# Mainboard.net
KiCad netlist of a schematic drawn in Altium Designer
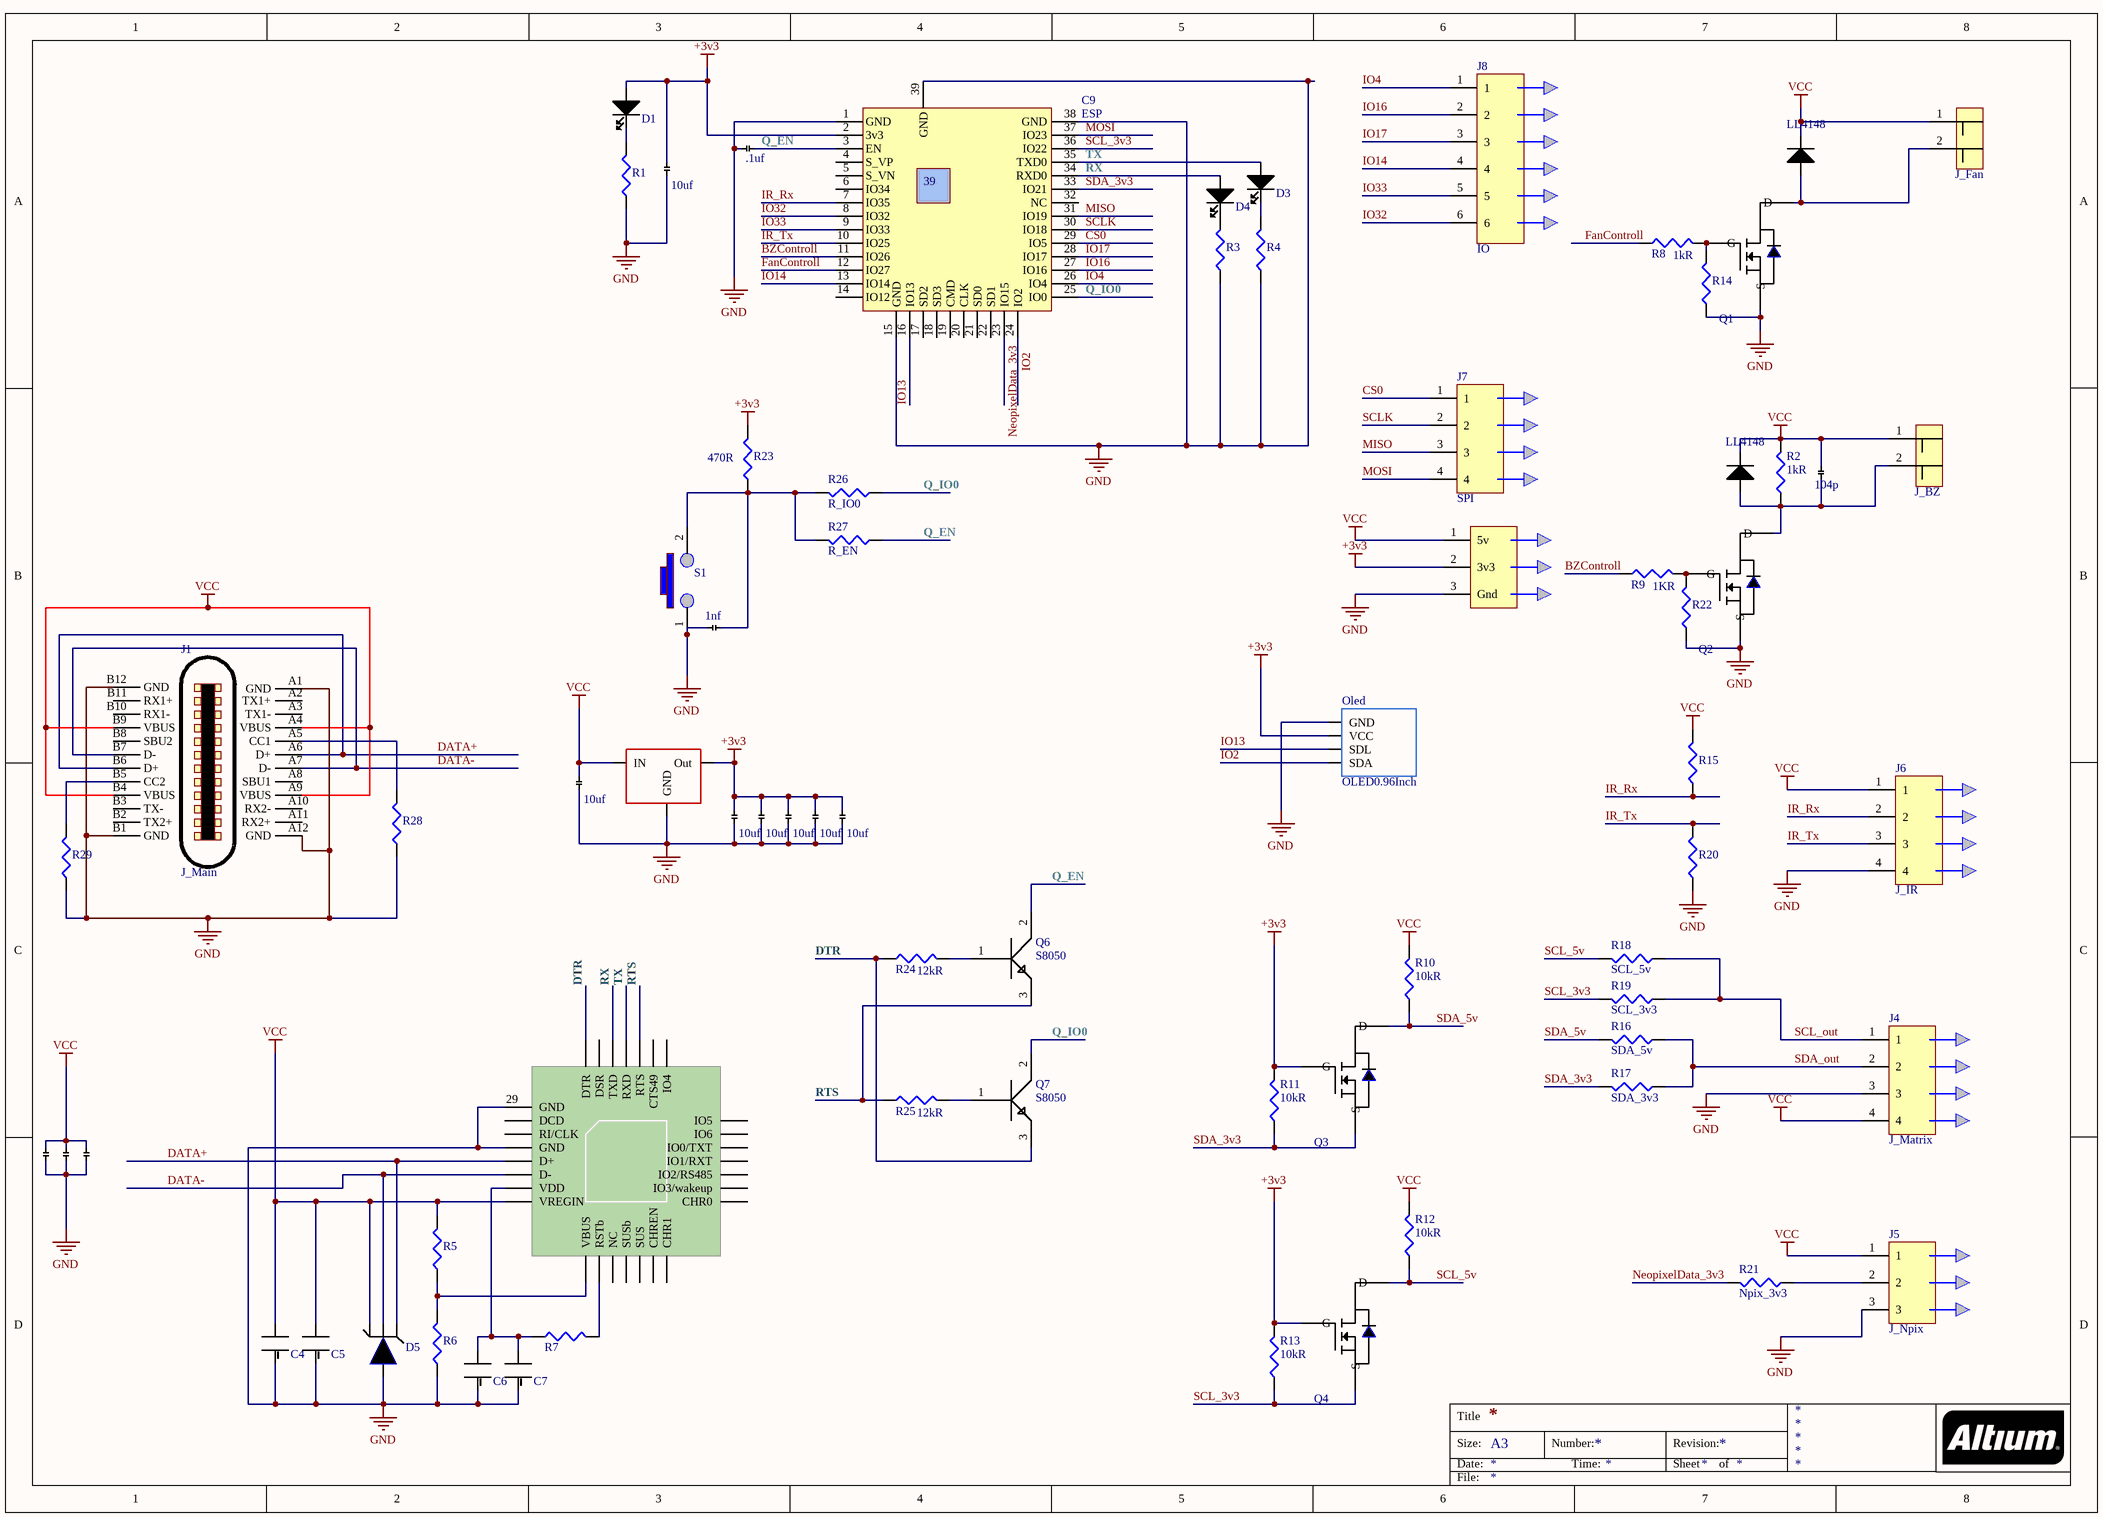
[diagram p0: Mainboard.SchDoc]

(export (version "E")
  (design (tool "Eeschema 10.0.6"))
  (components
    (comp (ref "C1")
      (value "104p")
      (footprint "Capacitor0805")
      (description "for leds and smol")
      (libsource (lib "WolfgasmScheLib") (part "capacitor0.1uf"))
    )
    (comp (ref "C2")
      (value "104p")
      (footprint "Capacitor0805")
      (description "for leds and smol")
      (libsource (lib "WolfgasmScheLib") (part "capacitor0.1uf"))
    )
    (comp (ref "C3")
      (value "104p")
      (footprint "Capacitor0805")
      (description "for leds and smol")
      (libsource (lib "WolfgasmScheLib") (part "capacitor0.1uf"))
    )
    (comp (ref "C4")
      (value "C4R7")
      (footprint "Capacitor0603")
      (description "Cap Ceramic 4.7uF 6.3V X5R 20% Pad SMD 0402 85C T/R")
      (fields (field (name "TOLERANCE") "20%"))
      (libsource (lib "WTFschlibra") (part "capacitor0603"))
    )
    (comp (ref "C5")
      (value "C104")
      (footprint "Capacitor0603")
      (description "0.1uf")
      (fields (field (name "TOLERANCE") "20%"))
      (libsource (lib "WTFschlibra") (part "capacitor0603"))
    )
    (comp (ref "C6")
      (value "C104")
      (footprint "Capacitor0603")
      (description "4.7")
      (fields (field (name "TOLERANCE") "20%"))
      (libsource (lib "WTFschlibra") (part "capacitor0603"))
    )
    (comp (ref "C7")
      (value "C4R7")
      (footprint "Capacitor0603")
      (description "0.1")
      (fields (field (name "TOLERANCE") "20%"))
      (libsource (lib "WTFschlibra") (part "capacitor0603"))
    )
    (comp (ref "C8")
      (value "104p")
      (footprint "Capacitor0805")
      (description "for leds and smol")
      (libsource (lib "WolfgasmScheLib") (part "capacitor0.1uf"))
    )
    (comp (ref "C9")
      (value "ESP")
      (footprint "ESP_WROOM_32_BARED_CHIP")
      (libsource (lib "WolfgasmScheLib") (part "ESP_wroom32_bared_chip"))
    )
    (comp (ref "C10")
      (value "1nf")
      (footprint "Capacitor0805")
      (description "for leds and smol")
      (libsource (lib "WolfgasmScheLib") (part "capacitor0.1uf"))
    )
    (comp (ref "C11")
      (value "10uf")
      (footprint "Capacitor0805")
      (description "for leds and smol")
      (libsource (lib "WolfgasmScheLib") (part "capacitor0.1uf"))
    )
    (comp (ref "C12")
      (value "10uf")
      (footprint "Capacitor0805")
      (description "for leds and smol")
      (libsource (lib "WolfgasmScheLib") (part "capacitor0.1uf"))
    )
    (comp (ref "C13")
      (value "10uf")
      (footprint "Capacitor0805")
      (description "for leds and smol")
      (libsource (lib "WolfgasmScheLib") (part "capacitor0.1uf"))
    )
    (comp (ref "C14")
      (value "10uf")
      (footprint "Capacitor0805")
      (description "for leds and smol")
      (libsource (lib "WolfgasmScheLib") (part "capacitor0.1uf"))
    )
    (comp (ref "C15")
      (value "10uf")
      (footprint "Capacitor0805")
      (description "for leds and smol")
      (libsource (lib "WolfgasmScheLib") (part "capacitor0.1uf"))
    )
    (comp (ref "C16")
      (value "10uf")
      (footprint "Capacitor0805")
      (description "for leds and smol")
      (libsource (lib "WolfgasmScheLib") (part "capacitor0.1uf"))
    )
    (comp (ref "C17")
      (value "10uf")
      (footprint "Capacitor0805")
      (description "for leds and smol")
      (libsource (lib "WolfgasmScheLib") (part "capacitor0.1uf"))
    )
    (comp (ref "C18")
      (value ".1uf")
      (footprint "Capacitor0805")
      (description "for leds and smol")
      (libsource (lib "WolfgasmScheLib") (part "capacitor0.1uf"))
    )
    (comp (ref "cp1")
      (value "CP2102N")
      (footprint "CP2102N_QFN28")
      (description "Full Speed USB to UART Bridge USB 2.0 3.3V T/R Automotive 28-Pin QFN EP")
      (libsource (lib "WTFschlibra") (part "CP2102N-A02-GQFN28R"))
    )
    (comp (ref "D1")
      (value "ESP")
      (footprint "LED0603")
      (description "LED BLUE CLEAR CHIP SMD")
      (libsource (lib "WTFschlibra") (part "LTST-C190TBKT"))
    )
    (comp (ref "D2")
      (value "LL4148")
      (footprint "SOD80-LL4148")
      (description "ON SEMICONDUCTOR - LL4148 - Small Signal Diode, Single, 100 V, 200 mA, 1 V, 4 ns, 2 A")
      (fields (field (name "VOLTAGE") "100V"))
      (libsource (lib "WolfgasmScheLib") (part "LL4148"))
    )
    (comp (ref "D3")
      (value "TXD")
      (footprint "LED0603")
      (description "LED BLUE CLEAR CHIP SMD")
      (libsource (lib "WTFschlibra") (part "LTST-C190TBKT"))
    )
    (comp (ref "D4")
      (value "RXD")
      (footprint "LED0603")
      (description "LED BLUE CLEAR CHIP SMD")
      (libsource (lib "WTFschlibra") (part "LTST-C190TBKT"))
    )
    (comp (ref "D5")
      (value "SP0503BAHTG")
      (footprint "SP0503BAHTG - SOT143-4")
      (description "ESD Suppressor TVS 5.5V 4-Pin(3+Tab) SOT-143 T/R")
      (libsource (lib "WTFschlibra") (part "SP0503BAHTG"))
    )
    (comp (ref "D6")
      (value "LL4148")
      (footprint "SOD80-LL4148")
      (description "ON SEMICONDUCTOR - LL4148 - Small Signal Diode, Single, 100 V, 200 mA, 1 V, 4 ns, 2 A")
      (fields (field (name "VOLTAGE") "100V"))
      (libsource (lib "WolfgasmScheLib") (part "LL4148"))
    )
    (comp (ref "J1")
      (value "J_Main")
      (footprint "USB_C_24P_SMT")
      (libsource (lib "WolfgasmScheLib") (part "USB_TypeC_24P"))
    )
    (comp (ref "J2")
      (value "J_BZ")
      (footprint "1x2 S2B-XH")
      (libsource (lib "WolfgasmScheLib") (part "S2B-XH"))
    )
    (comp (ref "J3")
      (value "J_Fan")
      (footprint "1x2 S2B-XH")
      (libsource (lib "WolfgasmScheLib") (part "S2B-XH"))
    )
    (comp (ref "J4")
      (value "J_Matrix")
      (footprint "1x4 DUPONT RightAngle")
      (libsource (lib "WolfgasmScheLib") (part "1x4 dupont general"))
    )
    (comp (ref "J5")
      (value "J_Npix")
      (footprint "1x3 2.54 big chunk verticle")
      (libsource (lib "WolfgasmScheLib") (part "1x3 2.54 chunk verticle"))
    )
    (comp (ref "J6")
      (value "J_IR")
      (footprint "Xh 2.54 4 Pin Right")
      (libsource (lib "WolfgasmScheLib") (part "1x4 general Header"))
    )
    (comp (ref "J7")
      (value "SPI")
      (footprint "1x4 DUPONT RightAngle")
      (libsource (lib "WolfgasmScheLib") (part "1x4 general Header"))
    )
    (comp (ref "J8")
      (value "IO")
      (footprint "1x6 dupont right angle")
      (libsource (lib "WolfgasmScheLib") (part "1x6 general dupont"))
    )
    (comp (ref "J9")
      (value "power")
      (footprint "1x3 dupont right angle")
      (libsource (lib "WolfgasmScheLib") (part "1x3 dupont power"))
    )
    (comp (ref "Oled")
      (value "OLED0.96Inch")
      (footprint "0.96OLED")
      (libsource (lib "WolfgasmScheLib") (part "OLED0.96Inch"))
    )
    (comp (ref "Q1")
      (value "Bss133")
      (footprint "SOT_23")
      (libsource (lib "WolfgasmScheLib") (part "Bss138 Mosfet"))
    )
    (comp (ref "Q2")
      (value "Bss133")
      (footprint "SOT_23")
      (libsource (lib "WolfgasmScheLib") (part "Bss138 Mosfet"))
    )
    (comp (ref "Q3")
      (value "Bss133")
      (footprint "SOT_23")
      (libsource (lib "WolfgasmScheLib") (part "Bss138 Mosfet"))
    )
    (comp (ref "Q4")
      (value "Bss133")
      (footprint "SOT_23")
      (libsource (lib "WolfgasmScheLib") (part "Bss138 Mosfet"))
    )
    (comp (ref "Q5")
      (value "lm1117")
      (footprint "SOT-223")
      (libsource (lib "WolfgasmScheLib") (part "LM1117-3.3v"))
    )
    (comp (ref "Q6")
      (value "S8050")
      (footprint "SOT_23")
      (libsource (lib "WolfgasmScheLib") (part "S8050NPN"))
    )
    (comp (ref "Q7")
      (value "S8050")
      (footprint "SOT_23")
      (libsource (lib "WolfgasmScheLib") (part "S8050NPN"))
    )
    (comp (ref "R1")
      (value "360R")
      (footprint "R0805")
      (description "Res Thick Film 0805 360 Ohm 1% 0.125W(1/8W) ±100ppm/C Molded SMD Automotive Paper T/R")
      (fields (field (name "TOLERANCE") "1%"))
      (libsource (lib "WTFschlibra") (part "CRCW0805360RFKEA"))
    )
    (comp (ref "R2")
      (value "1kR")
      (footprint "R0805")
      (description "Res Thick Film 0805 360 Ohm 1% 0.125W(1/8W) ±100ppm/C Molded SMD Automotive Paper T/R")
      (fields (field (name "TOLERANCE") "1%"))
      (libsource (lib "WolfgasmScheLib") (part "resistor(CRCW0805360RFKEA"))
    )
    (comp (ref "R3")
      (value "R360")
      (footprint "R0805")
      (description "Res Thick Film 0805 360 Ohm 1% 0.125W(1/8W) ±100ppm/C Molded SMD Automotive Paper T/R")
      (fields (field (name "TOLERANCE") "1%"))
      (libsource (lib "WTFschlibra") (part "CRCW0805360RFKEA"))
    )
    (comp (ref "R4")
      (value "R360")
      (footprint "R0805")
      (description "Res Thick Film 0805 360 Ohm 1% 0.125W(1/8W) ±100ppm/C Molded SMD Automotive Paper T/R")
      (fields (field (name "TOLERANCE") "1%"))
      (libsource (lib "WTFschlibra") (part "CRCW0805360RFKEA"))
    )
    (comp (ref "R5")
      (value "R2212")
      (footprint "R0805")
      (description "Res Thick Film 0805 360 Ohm 1% 0.125W(1/8W) ±100ppm/C Molded SMD Automotive Paper T/R")
      (fields (field (name "TOLERANCE") "1%"))
      (libsource (lib "WTFschlibra") (part "resistor(CRCW0805360RFKEA"))
    )
    (comp (ref "R6")
      (value "R4752")
      (footprint "R0805")
      (description "Res Thick Film 0805 360 Ohm 1% 0.125W(1/8W) ±100ppm/C Molded SMD Automotive Paper T/R")
      (fields (field (name "TOLERANCE") "1%"))
      (libsource (lib "WTFschlibra") (part "resistor(CRCW0805360RFKEA"))
    )
    (comp (ref "R7")
      (value "R102")
      (footprint "R0805")
      (description "1Kohms")
      (fields (field (name "TOLERANCE") "1%"))
      (libsource (lib "WTFschlibra") (part "resistor(CRCW0805360RFKEA"))
    )
    (comp (ref "R8")
      (value "1kR")
      (footprint "R0805")
      (description "Res Thick Film 0805 360 Ohm 1% 0.125W(1/8W) ±100ppm/C Molded SMD Automotive Paper T/R")
      (fields (field (name "TOLERANCE") "1%"))
      (libsource (lib "WolfgasmScheLib") (part "resistor(CRCW0805360RFKEA"))
    )
    (comp (ref "R9")
      (value "1KR")
      (footprint "R0805")
      (description "Res Thick Film 0805 360 Ohm 1% 0.125W(1/8W) ±100ppm/C Molded SMD Automotive Paper T/R")
      (fields (field (name "TOLERANCE") "1%"))
      (libsource (lib "WolfgasmScheLib") (part "resistor(CRCW0805360RFKEA"))
    )
    (comp (ref "R10")
      (value "10kR")
      (footprint "R0805")
      (description "Res Thick Film 0805 360 Ohm 1% 0.125W(1/8W) ±100ppm/C Molded SMD Automotive Paper T/R")
      (fields (field (name "TOLERANCE") "1%"))
      (libsource (lib "WolfgasmScheLib") (part "resistor(CRCW0805360RFKEA"))
    )
    (comp (ref "R11")
      (value "10kR")
      (footprint "R0805")
      (description "Res Thick Film 0805 360 Ohm 1% 0.125W(1/8W) ±100ppm/C Molded SMD Automotive Paper T/R")
      (fields (field (name "TOLERANCE") "1%"))
      (libsource (lib "WolfgasmScheLib") (part "resistor(CRCW0805360RFKEA"))
    )
    (comp (ref "R12")
      (value "10kR")
      (footprint "R0805")
      (description "Res Thick Film 0805 360 Ohm 1% 0.125W(1/8W) ±100ppm/C Molded SMD Automotive Paper T/R")
      (fields (field (name "TOLERANCE") "1%"))
      (libsource (lib "WolfgasmScheLib") (part "resistor(CRCW0805360RFKEA"))
    )
    (comp (ref "R13")
      (value "10kR")
      (footprint "R0805")
      (description "Res Thick Film 0805 360 Ohm 1% 0.125W(1/8W) ±100ppm/C Molded SMD Automotive Paper T/R")
      (fields (field (name "TOLERANCE") "1%"))
      (libsource (lib "WolfgasmScheLib") (part "resistor(CRCW0805360RFKEA"))
    )
    (comp (ref "R14")
      (value "10kR")
      (footprint "R0805")
      (description "Res Thick Film 0805 360 Ohm 1% 0.125W(1/8W) ±100ppm/C Molded SMD Automotive Paper T/R")
      (fields (field (name "TOLERANCE") "1%"))
      (libsource (lib "WTFschlibra") (part "CRCW0805360RFKEA"))
    )
    (comp (ref "R15")
      (value "10kR")
      (footprint "R0805")
      (description "Res Thick Film 0805 360 Ohm 1% 0.125W(1/8W) ±100ppm/C Molded SMD Automotive Paper T/R")
      (fields (field (name "TOLERANCE") "1%"))
      (libsource (lib "WTFschlibra") (part "CRCW0805360RFKEA"))
    )
    (comp (ref "R16")
      (value "SDA_5v")
      (footprint "R0805")
      (description "Res Thick Film 0805 360 Ohm 1% 0.125W(1/8W) ±100ppm/C Molded SMD Automotive Paper T/R")
      (fields (field (name "TOLERANCE") "1%"))
      (libsource (lib "WolfgasmScheLib") (part "resistor(CRCW0805360RFKEA"))
    )
    (comp (ref "R17")
      (value "SDA_3v3")
      (footprint "R0805")
      (description "Res Thick Film 0805 360 Ohm 1% 0.125W(1/8W) ±100ppm/C Molded SMD Automotive Paper T/R")
      (fields (field (name "TOLERANCE") "1%"))
      (libsource (lib "WolfgasmScheLib") (part "resistor(CRCW0805360RFKEA"))
    )
    (comp (ref "R18")
      (value "SCL_5v")
      (footprint "R0805")
      (description "Res Thick Film 0805 360 Ohm 1% 0.125W(1/8W) ±100ppm/C Molded SMD Automotive Paper T/R")
      (fields (field (name "TOLERANCE") "1%"))
      (libsource (lib "WolfgasmScheLib") (part "resistor(CRCW0805360RFKEA"))
    )
    (comp (ref "R19")
      (value "SCL_3v3")
      (footprint "R0805")
      (description "Res Thick Film 0805 360 Ohm 1% 0.125W(1/8W) ±100ppm/C Molded SMD Automotive Paper T/R")
      (fields (field (name "TOLERANCE") "1%"))
      (libsource (lib "WolfgasmScheLib") (part "resistor(CRCW0805360RFKEA"))
    )
    (comp (ref "R20")
      (value "10kR")
      (footprint "R0805")
      (description "Res Thick Film 0805 360 Ohm 1% 0.125W(1/8W) ±100ppm/C Molded SMD Automotive Paper T/R")
      (fields (field (name "TOLERANCE") "1%"))
      (libsource (lib "WTFschlibra") (part "CRCW0805360RFKEA"))
    )
    (comp (ref "R21")
      (value "Npix_3v3")
      (footprint "R0805")
      (description "Res Thick Film 0805 360 Ohm 1% 0.125W(1/8W) ±100ppm/C Molded SMD Automotive Paper T/R")
      (fields (field (name "TOLERANCE") "1%"))
      (libsource (lib "WolfgasmScheLib") (part "resistor(CRCW0805360RFKEA"))
    )
    (comp (ref "R22")
      (value "10kR")
      (footprint "R0805")
      (description "Res Thick Film 0805 360 Ohm 1% 0.125W(1/8W) ±100ppm/C Molded SMD Automotive Paper T/R")
      (fields (field (name "TOLERANCE") "1%"))
      (libsource (lib "WTFschlibra") (part "CRCW0805360RFKEA"))
    )
    (comp (ref "R23")
      (value "470R")
      (footprint "R0805")
      (description "Res Thick Film 0805 360 Ohm 1% 0.125W(1/8W) ±100ppm/C Molded SMD Automotive Paper T/R")
      (fields (field (name "TOLERANCE") "1%"))
      (libsource (lib "WTFschlibra") (part "CRCW0805360RFKEA"))
    )
    (comp (ref "R24")
      (value "12kR")
      (footprint "R0805")
      (description "Res Thick Film 0805 360 Ohm 1% 0.125W(1/8W) ±100ppm/C Molded SMD Automotive Paper T/R")
      (fields (field (name "TOLERANCE") "1%"))
      (libsource (lib "WolfgasmScheLib") (part "resistor(CRCW0805360RFKEA"))
    )
    (comp (ref "R25")
      (value "12kR")
      (footprint "R0805")
      (description "Res Thick Film 0805 360 Ohm 1% 0.125W(1/8W) ±100ppm/C Molded SMD Automotive Paper T/R")
      (fields (field (name "TOLERANCE") "1%"))
      (libsource (lib "WolfgasmScheLib") (part "resistor(CRCW0805360RFKEA"))
    )
    (comp (ref "R26")
      (value "R_IO0")
      (footprint "R0805")
      (description "Res Thick Film 0805 360 Ohm 1% 0.125W(1/8W) ±100ppm/C Molded SMD Automotive Paper T/R")
      (fields (field (name "TOLERANCE") "1%"))
      (libsource (lib "WTFschlibra") (part "CRCW0805360RFKEA"))
    )
    (comp (ref "R27")
      (value "R_EN")
      (footprint "R0805")
      (description "Res Thick Film 0805 360 Ohm 1% 0.125W(1/8W) ±100ppm/C Molded SMD Automotive Paper T/R")
      (fields (field (name "TOLERANCE") "1%"))
      (libsource (lib "WTFschlibra") (part "CRCW0805360RFKEA"))
    )
    (comp (ref "R28")
      (value "R5.1k")
      (footprint "R0805")
      (description "Res Thick Film 0805 360 Ohm 1% 0.125W(1/8W) ±100ppm/C Molded SMD Automotive Paper T/R")
      (fields (field (name "TOLERANCE") "1%"))
      (libsource (lib "WTFschlibra") (part "resistor(CRCW0805360RFKEA"))
    )
    (comp (ref "R29")
      (value "R5.1k")
      (footprint "R0805")
      (description "Res Thick Film 0805 360 Ohm 1% 0.125W(1/8W) ±100ppm/C Molded SMD Automotive Paper T/R")
      (fields (field (name "TOLERANCE") "1%"))
      (libsource (lib "WTFschlibra") (part "resistor(CRCW0805360RFKEA"))
    )
    (comp (ref "S1") (value "RST") (libsource (lib "WolfgasmScheLib") (part "Smol_switch")))
  )
  (nets
    (net (code "1") (name "+3v3") (class "Default")
      (node (ref "C12") (pin "1") (pinfunction "-_1") (pintype "passive"))
      (node (ref "C13") (pin "1") (pinfunction "-_1") (pintype "passive"))
      (node (ref "C14") (pin "1") (pinfunction "-_1") (pintype "passive"))
      (node (ref "C15") (pin "1") (pinfunction "-_1") (pintype "passive"))
      (node (ref "C16") (pin "1") (pinfunction "-_1") (pintype "passive"))
      (node (ref "C17") (pin "1") (pinfunction "-_1") (pintype "passive"))
      (node (ref "C9") (pin "2") (pinfunction "3v3_2") (pintype "passive"))
      (node (ref "D1") (pin "2") (pinfunction "2_2") (pintype "passive"))
      (node (ref "J9") (pin "2") (pinfunction "3v3_2") (pintype "passive"))
      (node (ref "Oled") (pin "2") (pinfunction "VCC_2") (pintype "passive"))
      (node (ref "Q3") (pin "1") (pinfunction "G_1") (pintype "passive"))
      (node (ref "Q4") (pin "1") (pinfunction "G_1") (pintype "passive"))
      (node (ref "Q5") (pin "2") (pinfunction "Out_2") (pintype "passive"))
      (node (ref "R11") (pin "2") (pinfunction "2_2") (pintype "passive"))
      (node (ref "R13") (pin "2") (pinfunction "2_2") (pintype "passive"))
      (node (ref "R23") (pin "2") (pinfunction "2_2") (pintype "passive"))
    )
    (net (code "2") (name "/BZControll") (class "Default")
      (node (ref "C9") (pin "11") (pinfunction "IO26_11") (pintype "passive"))
      (node (ref "R9") (pin "1") (pinfunction "1_1") (pintype "passive"))
    )
    (net (code "3") (name "/CS0") (class "Default")
      (node (ref "C9") (pin "29") (pinfunction "IO5_29") (pintype "passive"))
      (node (ref "J7") (pin "1") (pinfunction "1_1") (pintype "passive"))
    )
    (net (code "4") (name "/DATA+") (class "Default")
      (node (ref "D5") (pin "2") (pinfunction "2_2") (pintype "passive"))
      (node (ref "J1") (pin "A6") (pinfunction "D+_A6") (pintype "passive"))
      (node (ref "J1") (pin "B6") (pinfunction "D+_B6") (pintype "passive"))
      (node (ref "cp1") (pin "4") (pinfunction "D+_4") (pintype "passive"))
    )
    (net (code "5") (name "/DATA-") (class "Default")
      (node (ref "D5") (pin "3") (pinfunction "3_3") (pintype "passive"))
      (node (ref "J1") (pin "A7") (pinfunction "D-_A7") (pintype "passive"))
      (node (ref "J1") (pin "B7") (pinfunction "D-_B7") (pintype "passive"))
      (node (ref "cp1") (pin "5") (pinfunction "D-_5") (pintype "passive"))
    )
    (net (code "6") (name "/DTR") (class "Default")
      (node (ref "Q7") (pin "3") (pinfunction "3_3") (pintype "passive"))
      (node (ref "R24") (pin "1") (pinfunction "1_1") (pintype "passive"))
      (node (ref "cp1") (pin "28") (pinfunction "DTR_28") (pintype "passive"))
    )
    (net (code "7") (name "/FanControll") (class "Default")
      (node (ref "C9") (pin "12") (pinfunction "IO27_12") (pintype "passive"))
      (node (ref "R8") (pin "1") (pinfunction "1_1") (pintype "passive"))
    )
    (net (code "8") (name "/IO2") (class "Default")
      (node (ref "C9") (pin "24") (pinfunction "IO2_24") (pintype "passive"))
      (node (ref "Oled") (pin "4") (pinfunction "SDA_4") (pintype "passive"))
    )
    (net (code "9") (name "/IO4") (class "Default")
      (node (ref "C9") (pin "26") (pinfunction "IO4_26") (pintype "passive"))
      (node (ref "J8") (pin "1") (pinfunction "1_1") (pintype "passive"))
    )
    (net (code "10") (name "/IO13") (class "Default")
      (node (ref "C9") (pin "16") (pinfunction "IO13_16") (pintype "passive"))
      (node (ref "Oled") (pin "3") (pinfunction "SDL_3") (pintype "passive"))
    )
    (net (code "11") (name "/IO14") (class "Default")
      (node (ref "C9") (pin "13") (pinfunction "IO14_13") (pintype "passive"))
      (node (ref "J8") (pin "4") (pinfunction "4_4") (pintype "passive"))
    )
    (net (code "12") (name "/IO16") (class "Default")
      (node (ref "C9") (pin "27") (pinfunction "IO16_27") (pintype "passive"))
      (node (ref "J8") (pin "2") (pinfunction "2_2") (pintype "passive"))
    )
    (net (code "13") (name "/IO17") (class "Default")
      (node (ref "C9") (pin "28") (pinfunction "IO17_28") (pintype "passive"))
      (node (ref "J8") (pin "3") (pinfunction "3_3") (pintype "passive"))
    )
    (net (code "14") (name "/IO32") (class "Default")
      (node (ref "C9") (pin "8") (pinfunction "IO32_8") (pintype "passive"))
      (node (ref "J8") (pin "6") (pinfunction "6_6") (pintype "passive"))
    )
    (net (code "15") (name "/IO33") (class "Default")
      (node (ref "C9") (pin "9") (pinfunction "IO33_9") (pintype "passive"))
      (node (ref "J8") (pin "5") (pinfunction "5_5") (pintype "passive"))
    )
    (net (code "16") (name "/IR_Rx") (class "Default")
      (node (ref "C9") (pin "7") (pinfunction "IO35_7") (pintype "passive"))
      (node (ref "J6") (pin "2") (pinfunction "2_2") (pintype "passive"))
      (node (ref "R15") (pin "1") (pinfunction "1_1") (pintype "passive"))
    )
    (net (code "17") (name "/IR_Tx") (class "Default")
      (node (ref "C9") (pin "10") (pinfunction "IO25_10") (pintype "passive"))
      (node (ref "J6") (pin "3") (pinfunction "3_3") (pintype "passive"))
      (node (ref "R20") (pin "2") (pinfunction "2_2") (pintype "passive"))
    )
    (net (code "18") (name "/MISO") (class "Default")
      (node (ref "C9") (pin "31") (pinfunction "IO19_31") (pintype "passive"))
      (node (ref "J7") (pin "3") (pinfunction "3_3") (pintype "passive"))
    )
    (net (code "19") (name "/MOSI") (class "Default")
      (node (ref "C9") (pin "37") (pinfunction "IO23_37") (pintype "passive"))
      (node (ref "J7") (pin "4") (pinfunction "4_4") (pintype "passive"))
    )
    (net (code "20") (name "/NeopixelData_3v3") (class "Default")
      (node (ref "C9") (pin "23") (pinfunction "IO15_23") (pintype "passive"))
      (node (ref "R21") (pin "2") (pinfunction "2_2") (pintype "passive"))
    )
    (net (code "21") (name "/Q_EN") (class "Default")
      (node (ref "C18") (pin "2") (pinfunction "+_2") (pintype "passive"))
      (node (ref "C9") (pin "3") (pinfunction "EN_3") (pintype "passive"))
      (node (ref "Q6") (pin "2") (pinfunction "2_2") (pintype "passive"))
      (node (ref "R27") (pin "1") (pinfunction "1_1") (pintype "passive"))
    )
    (net (code "22") (name "/Q_IO0") (class "Default")
      (node (ref "C9") (pin "25") (pinfunction "IO0_25") (pintype "passive"))
      (node (ref "Q7") (pin "2") (pinfunction "2_2") (pintype "passive"))
      (node (ref "R26") (pin "1") (pinfunction "1_1") (pintype "passive"))
    )
    (net (code "23") (name "/RTS") (class "Default")
      (node (ref "Q6") (pin "3") (pinfunction "3_3") (pintype "passive"))
      (node (ref "R25") (pin "1") (pinfunction "1_1") (pintype "passive"))
      (node (ref "cp1") (pin "24") (pinfunction "RTS_24") (pintype "passive"))
    )
    (net (code "24") (name "/RX") (class "Default")
      (node (ref "C9") (pin "34") (pinfunction "RXD0_34") (pintype "passive"))
      (node (ref "D4") (pin "2") (pinfunction "2_2") (pintype "passive"))
      (node (ref "cp1") (pin "26") (pinfunction "TXD_26") (pintype "passive"))
    )
    (net (code "25") (name "/SCLK") (class "Default")
      (node (ref "C9") (pin "30") (pinfunction "IO18_30") (pintype "passive"))
      (node (ref "J7") (pin "2") (pinfunction "2_2") (pintype "passive"))
    )
    (net (code "26") (name "/SCL_3v3") (class "Default")
      (node (ref "C9") (pin "36") (pinfunction "IO22_36") (pintype "passive"))
      (node (ref "Q4") (pin "3") (pinfunction "S_3") (pintype "passive"))
      (node (ref "R13") (pin "1") (pinfunction "1_1") (pintype "passive"))
      (node (ref "R19") (pin "2") (pinfunction "2_2") (pintype "passive"))
    )
    (net (code "27") (name "/SCL_5v") (class "Default")
      (node (ref "Q4") (pin "2") (pinfunction "D_2") (pintype "passive"))
      (node (ref "R12") (pin "1") (pinfunction "1_1") (pintype "passive"))
      (node (ref "R18") (pin "2") (pinfunction "2_2") (pintype "passive"))
    )
    (net (code "28") (name "/SCL_out") (class "Default")
      (node (ref "J4") (pin "1") (pinfunction "1_1") (pintype "passive"))
      (node (ref "R18") (pin "1") (pinfunction "1_1") (pintype "passive"))
      (node (ref "R19") (pin "1") (pinfunction "1_1") (pintype "passive"))
    )
    (net (code "29") (name "/SDA_3v3") (class "Default")
      (node (ref "C9") (pin "33") (pinfunction "IO21_33") (pintype "passive"))
      (node (ref "Q3") (pin "3") (pinfunction "S_3") (pintype "passive"))
      (node (ref "R11") (pin "1") (pinfunction "1_1") (pintype "passive"))
      (node (ref "R17") (pin "2") (pinfunction "2_2") (pintype "passive"))
    )
    (net (code "30") (name "/SDA_5v") (class "Default")
      (node (ref "Q3") (pin "2") (pinfunction "D_2") (pintype "passive"))
      (node (ref "R10") (pin "1") (pinfunction "1_1") (pintype "passive"))
      (node (ref "R16") (pin "2") (pinfunction "2_2") (pintype "passive"))
    )
    (net (code "31") (name "/SDA_out") (class "Default")
      (node (ref "J4") (pin "2") (pinfunction "2_2") (pintype "passive"))
      (node (ref "R16") (pin "1") (pinfunction "1_1") (pintype "passive"))
      (node (ref "R17") (pin "1") (pinfunction "1_1") (pintype "passive"))
    )
    (net (code "32") (name "/TX") (class "Default")
      (node (ref "C9") (pin "35") (pinfunction "TXD0_35") (pintype "passive"))
      (node (ref "D3") (pin "2") (pinfunction "2_2") (pintype "passive"))
      (node (ref "cp1") (pin "25") (pinfunction "RXD_25") (pintype "passive"))
    )
    (net (code "33") (name "GND") (class "Default")
      (node (ref "C10") (pin "2") (pinfunction "+_2") (pintype "passive"))
      (node (ref "C11") (pin "2") (pinfunction "+_2") (pintype "passive"))
      (node (ref "C12") (pin "2") (pinfunction "+_2") (pintype "passive"))
      (node (ref "C13") (pin "2") (pinfunction "+_2") (pintype "passive"))
      (node (ref "C14") (pin "2") (pinfunction "+_2") (pintype "passive"))
      (node (ref "C15") (pin "2") (pinfunction "+_2") (pintype "passive"))
      (node (ref "C16") (pin "2") (pinfunction "+_2") (pintype "passive"))
      (node (ref "C17") (pin "2") (pinfunction "+_2") (pintype "passive"))
      (node (ref "C18") (pin "1") (pinfunction "-_1") (pintype "passive"))
      (node (ref "C2") (pin "1") (pinfunction "-_1") (pintype "passive"))
      (node (ref "C3") (pin "1") (pinfunction "-_1") (pintype "passive"))
      (node (ref "C4") (pin "1") (pinfunction "-_1") (pintype "passive"))
      (node (ref "C5") (pin "1") (pinfunction "-_1") (pintype "passive"))
      (node (ref "C6") (pin "1") (pinfunction "-_1") (pintype "passive"))
      (node (ref "C7") (pin "1") (pinfunction "-_1") (pintype "passive"))
      (node (ref "C8") (pin "1") (pinfunction "-_1") (pintype "passive"))
      (node (ref "C9") (pin "1") (pinfunction "GND_1") (pintype "passive"))
      (node (ref "C9") (pin "15") (pinfunction "GND_15") (pintype "passive"))
      (node (ref "C9") (pin "38") (pinfunction "GND_38") (pintype "passive"))
      (node (ref "C9") (pin "39") (pinfunction "GND_39") (pintype "passive"))
      (node (ref "D5") (pin "1") (pinfunction "+_1") (pintype "passive"))
      (node (ref "J1") (pin "A1") (pinfunction "GND_A1") (pintype "passive"))
      (node (ref "J1") (pin "A12") (pinfunction "GND_A12") (pintype "passive"))
      (node (ref "J1") (pin "B1") (pinfunction "GND_B1") (pintype "passive"))
      (node (ref "J1") (pin "B12") (pinfunction "GND_B12") (pintype "passive"))
      (node (ref "J4") (pin "3") (pinfunction "3_3") (pintype "passive"))
      (node (ref "J5") (pin "3") (pinfunction "3_3") (pintype "passive"))
      (node (ref "J6") (pin "4") (pinfunction "4_4") (pintype "passive"))
      (node (ref "J9") (pin "3") (pinfunction "Gnd_3") (pintype "passive"))
      (node (ref "Oled") (pin "1") (pinfunction "GND_1") (pintype "passive"))
      (node (ref "Q1") (pin "3") (pinfunction "S_3") (pintype "passive"))
      (node (ref "Q2") (pin "3") (pinfunction "S_3") (pintype "passive"))
      (node (ref "Q5") (pin "1") (pinfunction "GND_1") (pintype "passive"))
      (node (ref "R1") (pin "1") (pinfunction "1_1") (pintype "passive"))
      (node (ref "R14") (pin "1") (pinfunction "1_1") (pintype "passive"))
      (node (ref "R20") (pin "1") (pinfunction "1_1") (pintype "passive"))
      (node (ref "R22") (pin "1") (pinfunction "1_1") (pintype "passive"))
      (node (ref "R28") (pin "1") (pinfunction "1_1") (pintype "passive"))
      (node (ref "R29") (pin "1") (pinfunction "1_1") (pintype "passive"))
      (node (ref "R3") (pin "1") (pinfunction "1_1") (pintype "passive"))
      (node (ref "R4") (pin "1") (pinfunction "1_1") (pintype "passive"))
      (node (ref "R6") (pin "1") (pinfunction "1_1") (pintype "passive"))
      (node (ref "S1") (pin "1") (pinfunction "1_1") (pintype "passive"))
      (node (ref "cp1") (pin "29") (pinfunction "GND_29") (pintype "passive"))
      (node (ref "cp1") (pin "3") (pinfunction "GND_3") (pintype "passive"))
    )
    (net (code "34") (name "Net-(C1--)") (class "Default")
      (node (ref "C1") (pin "1") (pinfunction "-_1") (pintype "passive"))
      (node (ref "D6") (pin "2") (pinfunction "2_2") (pintype "passive"))
      (node (ref "J2") (pin "2") (pinfunction "2_2") (pintype "passive"))
      (node (ref "Q2") (pin "2") (pinfunction "D_2") (pintype "passive"))
      (node (ref "R2") (pin "1") (pinfunction "1_1") (pintype "passive"))
    )
    (net (code "35") (name "Net-(C6-+)") (class "Default")
      (node (ref "C6") (pin "2") (pinfunction "+_2") (pintype "passive"))
      (node (ref "C7") (pin "2") (pinfunction "+_2") (pintype "passive"))
      (node (ref "R7") (pin "1") (pinfunction "1_1") (pintype "passive"))
      (node (ref "cp1") (pin "6") (pinfunction "VDD_6") (pintype "passive"))
    )
    (net (code "36") (name "Net-(C10--)") (class "Default")
      (node (ref "C10") (pin "1") (pinfunction "-_1") (pintype "passive"))
      (node (ref "R23") (pin "1") (pinfunction "1_1") (pintype "passive"))
      (node (ref "R26") (pin "2") (pinfunction "2_2") (pintype "passive"))
      (node (ref "R27") (pin "2") (pinfunction "2_2") (pintype "passive"))
      (node (ref "S1") (pin "2") (pinfunction "2_2") (pintype "passive"))
    )
    (net (code "37") (name "Net-(D1-Pad1)") (class "Default")
      (node (ref "D1") (pin "1") (pinfunction "1_1") (pintype "passive"))
      (node (ref "R1") (pin "2") (pinfunction "2_2") (pintype "passive"))
    )
    (net (code "38") (name "Net-(D3-Pad1)") (class "Default")
      (node (ref "D3") (pin "1") (pinfunction "1_1") (pintype "passive"))
      (node (ref "R4") (pin "2") (pinfunction "2_2") (pintype "passive"))
    )
    (net (code "39") (name "Net-(D4-Pad1)") (class "Default")
      (node (ref "D4") (pin "1") (pinfunction "1_1") (pintype "passive"))
      (node (ref "R3") (pin "2") (pinfunction "2_2") (pintype "passive"))
    )
    (net (code "40") (name "Net-(J1-CC1)") (class "Default")
      (node (ref "J1") (pin "A5") (pinfunction "CC1_A5") (pintype "passive"))
      (node (ref "R28") (pin "2") (pinfunction "2_2") (pintype "passive"))
    )
    (net (code "41") (name "Net-(J1-CC2)") (class "Default")
      (node (ref "J1") (pin "B5") (pinfunction "CC2_B5") (pintype "passive"))
      (node (ref "R29") (pin "2") (pinfunction "2_2") (pintype "passive"))
    )
    (net (code "42") (name "Net-(J5-Pad2)") (class "Default")
      (node (ref "J5") (pin "2") (pinfunction "2_2") (pintype "passive"))
      (node (ref "R21") (pin "1") (pinfunction "1_1") (pintype "passive"))
    )
    (net (code "43") (name "Net-(Q1-D)") (class "Default")
      (node (ref "D2") (pin "2") (pinfunction "2_2") (pintype "passive"))
      (node (ref "J3") (pin "2") (pinfunction "2_2") (pintype "passive"))
      (node (ref "Q1") (pin "2") (pinfunction "D_2") (pintype "passive"))
    )
    (net (code "44") (name "Net-(Q1-G)") (class "Default")
      (node (ref "Q1") (pin "1") (pinfunction "G_1") (pintype "passive"))
      (node (ref "R14") (pin "2") (pinfunction "2_2") (pintype "passive"))
      (node (ref "R8") (pin "2") (pinfunction "2_2") (pintype "passive"))
    )
    (net (code "45") (name "Net-(Q2-G)") (class "Default")
      (node (ref "Q2") (pin "1") (pinfunction "G_1") (pintype "passive"))
      (node (ref "R22") (pin "2") (pinfunction "2_2") (pintype "passive"))
      (node (ref "R9") (pin "2") (pinfunction "2_2") (pintype "passive"))
    )
    (net (code "46") (name "Net-(Q6-Pad1)") (class "Default")
      (node (ref "Q6") (pin "1") (pinfunction "1_1") (pintype "passive"))
      (node (ref "R24") (pin "2") (pinfunction "2_2") (pintype "passive"))
    )
    (net (code "47") (name "Net-(Q7-Pad1)") (class "Default")
      (node (ref "Q7") (pin "1") (pinfunction "1_1") (pintype "passive"))
      (node (ref "R25") (pin "2") (pinfunction "2_2") (pintype "passive"))
    )
    (net (code "48") (name "Net-(cp1-RSTb)") (class "Default")
      (node (ref "R7") (pin "2") (pinfunction "2_2") (pintype "passive"))
      (node (ref "cp1") (pin "9") (pinfunction "RSTb_9") (pintype "passive"))
    )
    (net (code "49") (name "Net-(cp1-VBUS)") (class "Default")
      (node (ref "R5") (pin "1") (pinfunction "1_1") (pintype "passive"))
      (node (ref "R6") (pin "2") (pinfunction "2_2") (pintype "passive"))
      (node (ref "cp1") (pin "8") (pinfunction "VBUS_8") (pintype "passive"))
    )
    (net (code "50") (name "VCC") (class "Default")
      (node (ref "C1") (pin "2") (pinfunction "+_2") (pintype "passive"))
      (node (ref "C11") (pin "1") (pinfunction "-_1") (pintype "passive"))
      (node (ref "C2") (pin "2") (pinfunction "+_2") (pintype "passive"))
      (node (ref "C3") (pin "2") (pinfunction "+_2") (pintype "passive"))
      (node (ref "C4") (pin "2") (pinfunction "+_2") (pintype "passive"))
      (node (ref "C5") (pin "2") (pinfunction "+_2") (pintype "passive"))
      (node (ref "C8") (pin "2") (pinfunction "+_2") (pintype "passive"))
      (node (ref "D2") (pin "1") (pinfunction "1_1") (pintype "passive"))
      (node (ref "D5") (pin "4") (pinfunction "4_4") (pintype "passive"))
      (node (ref "D6") (pin "1") (pinfunction "1_1") (pintype "passive"))
      (node (ref "J1") (pin "A4") (pinfunction "VBUS_A4") (pintype "passive"))
      (node (ref "J1") (pin "A9") (pinfunction "VBUS_A9") (pintype "passive"))
      (node (ref "J1") (pin "B4") (pinfunction "VBUS_B4") (pintype "passive"))
      (node (ref "J1") (pin "B9") (pinfunction "VBUS_B9") (pintype "passive"))
      (node (ref "J2") (pin "1") (pinfunction "1_1") (pintype "passive"))
      (node (ref "J3") (pin "1") (pinfunction "1_1") (pintype "passive"))
      (node (ref "J4") (pin "4") (pinfunction "4_4") (pintype "passive"))
      (node (ref "J5") (pin "1") (pinfunction "1_1") (pintype "passive"))
      (node (ref "J6") (pin "1") (pinfunction "1_1") (pintype "passive"))
      (node (ref "J9") (pin "1") (pinfunction "5v_1") (pintype "passive"))
      (node (ref "Q5") (pin "3") (pinfunction "IN_3") (pintype "passive"))
      (node (ref "R10") (pin "2") (pinfunction "2_2") (pintype "passive"))
      (node (ref "R12") (pin "2") (pinfunction "2_2") (pintype "passive"))
      (node (ref "R15") (pin "2") (pinfunction "2_2") (pintype "passive"))
      (node (ref "R2") (pin "2") (pinfunction "2_2") (pintype "passive"))
      (node (ref "R5") (pin "2") (pinfunction "2_2") (pintype "passive"))
      (node (ref "cp1") (pin "7") (pinfunction "VREGIN_7") (pintype "passive"))
    )
    (net (code "51") (name "unconnected-(C9-CLK-Pad20)") (class "Default")
      (node (ref "C9") (pin "20") (pinfunction "CLK_20") (pintype "passive"))
    )
    (net (code "52") (name "unconnected-(C9-CMD-Pad19)") (class "Default")
      (node (ref "C9") (pin "19") (pinfunction "CMD_19") (pintype "passive"))
    )
    (net (code "53") (name "unconnected-(C9-IO12-Pad14)") (class "Default")
      (node (ref "C9") (pin "14") (pinfunction "IO12_14") (pintype "passive"))
    )
    (net (code "54") (name "unconnected-(C9-IO34-Pad6)") (class "Default")
      (node (ref "C9") (pin "6") (pinfunction "IO34_6") (pintype "passive"))
    )
    (net (code "55") (name "unconnected-(C9-NC-Pad32)") (class "Default")
      (node (ref "C9") (pin "32") (pinfunction "NC_32") (pintype "passive"))
    )
    (net (code "56") (name "unconnected-(C9-SD0-Pad21)") (class "Default")
      (node (ref "C9") (pin "21") (pinfunction "SD0_21") (pintype "passive"))
    )
    (net (code "57") (name "unconnected-(C9-SD1-Pad22)") (class "Default")
      (node (ref "C9") (pin "22") (pinfunction "SD1_22") (pintype "passive"))
    )
    (net (code "58") (name "unconnected-(C9-SD2-Pad17)") (class "Default")
      (node (ref "C9") (pin "17") (pinfunction "SD2_17") (pintype "passive"))
    )
    (net (code "59") (name "unconnected-(C9-SD3-Pad18)") (class "Default")
      (node (ref "C9") (pin "18") (pinfunction "SD3_18") (pintype "passive"))
    )
    (net (code "60") (name "unconnected-(C9-S_VN-Pad5)") (class "Default")
      (node (ref "C9") (pin "5") (pinfunction "S_VN_5") (pintype "passive"))
    )
    (net (code "61") (name "unconnected-(C9-S_VP-Pad4)") (class "Default")
      (node (ref "C9") (pin "4") (pinfunction "S_VP_4") (pintype "passive"))
    )
    (net (code "62") (name "unconnected-(J1-RX1+-PadB11)") (class "Default")
      (node (ref "J1") (pin "B11") (pinfunction "RX1+_B11") (pintype "passive"))
    )
    (net (code "63") (name "unconnected-(J1-RX1--PadB10)") (class "Default")
      (node (ref "J1") (pin "B10") (pinfunction "RX1-_B10") (pintype "passive"))
    )
    (net (code "64") (name "unconnected-(J1-RX2+-PadA11)") (class "Default")
      (node (ref "J1") (pin "A11") (pinfunction "RX2+_A11") (pintype "passive"))
    )
    (net (code "65") (name "unconnected-(J1-RX2--PadA10)") (class "Default")
      (node (ref "J1") (pin "A10") (pinfunction "RX2-_A10") (pintype "passive"))
    )
    (net (code "66") (name "unconnected-(J1-SBU1-PadA8)") (class "Default")
      (node (ref "J1") (pin "A8") (pinfunction "SBU1_A8") (pintype "passive"))
    )
    (net (code "67") (name "unconnected-(J1-SBU2-PadB8)") (class "Default")
      (node (ref "J1") (pin "B8") (pinfunction "SBU2_B8") (pintype "passive"))
    )
    (net (code "68") (name "unconnected-(J1-TX--PadB3)") (class "Default")
      (node (ref "J1") (pin "B3") (pinfunction "TX-_B3") (pintype "passive"))
    )
    (net (code "69") (name "unconnected-(J1-TX1+-PadA2)") (class "Default")
      (node (ref "J1") (pin "A2") (pinfunction "TX1+_A2") (pintype "passive"))
    )
    (net (code "70") (name "unconnected-(J1-TX1--PadA3)") (class "Default")
      (node (ref "J1") (pin "A3") (pinfunction "TX1-_A3") (pintype "passive"))
    )
    (net (code "71") (name "unconnected-(J1-TX2+-PadB2)") (class "Default")
      (node (ref "J1") (pin "B2") (pinfunction "TX2+_B2") (pintype "passive"))
    )
    (net (code "72") (name "unconnected-(cp1-CHR0-Pad15)") (class "Default")
      (node (ref "cp1") (pin "15") (pinfunction "CHR0_15") (pintype "passive"))
    )
    (net (code "73") (name "unconnected-(cp1-CHR1-Pad14)") (class "Default")
      (node (ref "cp1") (pin "14") (pinfunction "CHR1_14") (pintype "passive"))
    )
    (net (code "74") (name "unconnected-(cp1-CHREN-Pad13)") (class "Default")
      (node (ref "cp1") (pin "13") (pinfunction "CHREN_13") (pintype "passive"))
    )
    (net (code "75") (name "unconnected-(cp1-CTS49-Pad23)") (class "Default")
      (node (ref "cp1") (pin "23") (pinfunction "CTS49_23") (pintype "passive"))
    )
    (net (code "76") (name "unconnected-(cp1-DCD-Pad1)") (class "Default")
      (node (ref "cp1") (pin "1") (pinfunction "DCD_1") (pintype "passive"))
    )
    (net (code "77") (name "unconnected-(cp1-DSR-Pad27)") (class "Default")
      (node (ref "cp1") (pin "27") (pinfunction "DSR_27") (pintype "passive"))
    )
    (net (code "78") (name "unconnected-(cp1-IO0{slash}TXT-Pad19)") (class "Default")
      (node (ref "cp1") (pin "19") (pinfunction "IO0/TXT_19") (pintype "passive"))
    )
    (net (code "79") (name "unconnected-(cp1-IO1{slash}RXT-Pad18)") (class "Default")
      (node (ref "cp1") (pin "18") (pinfunction "IO1/RXT_18") (pintype "passive"))
    )
    (net (code "80") (name "unconnected-(cp1-IO2{slash}RS485-Pad17)") (class "Default")
      (node (ref "cp1") (pin "17") (pinfunction "IO2/RS485_17") (pintype "passive"))
    )
    (net (code "81") (name "unconnected-(cp1-IO3{slash}wakeup-Pad16)") (class "Default")
      (node (ref "cp1") (pin "16") (pinfunction "IO3/wakeup_16") (pintype "passive"))
    )
    (net (code "82") (name "unconnected-(cp1-IO4-Pad22)") (class "Default")
      (node (ref "cp1") (pin "22") (pinfunction "IO4_22") (pintype "passive"))
    )
    (net (code "83") (name "unconnected-(cp1-IO5-Pad21)") (class "Default")
      (node (ref "cp1") (pin "21") (pinfunction "IO5_21") (pintype "passive"))
    )
    (net (code "84") (name "unconnected-(cp1-IO6-Pad20)") (class "Default")
      (node (ref "cp1") (pin "20") (pinfunction "IO6_20") (pintype "passive"))
    )
    (net (code "85") (name "unconnected-(cp1-NC-Pad10)") (class "Default")
      (node (ref "cp1") (pin "10") (pinfunction "NC_10") (pintype "passive"))
    )
    (net (code "86") (name "unconnected-(cp1-RI{slash}CLK-Pad2)") (class "Default")
      (node (ref "cp1") (pin "2") (pinfunction "RI/CLK_2") (pintype "passive"))
    )
    (net (code "87") (name "unconnected-(cp1-SUS-Pad12)") (class "Default")
      (node (ref "cp1") (pin "12") (pinfunction "SUS_12") (pintype "passive"))
    )
    (net (code "88") (name "unconnected-(cp1-SUSb-Pad11)") (class "Default")
      (node (ref "cp1") (pin "11") (pinfunction "SUSb_11") (pintype "passive"))
    )
  )
)
